# DB15.net
KiCad netlist of a schematic drawn in EAGLE
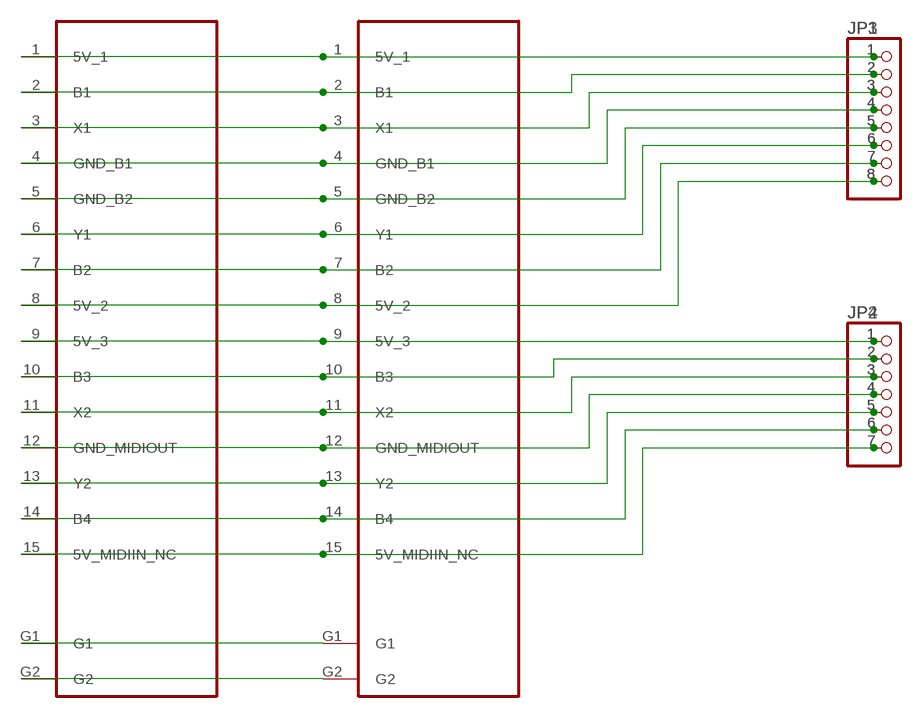
[diagram p0: schematic, sheet 1]

(export (version "E")
  (design (tool "Eeschema 10.0.6"))
  (components
    (comp (ref "JP1")
      (value "PINHD-1X8")
      (footprint "eagle-import:1X08")
      (libsource (lib "eagle-import") (part "PINHD-1X8"))
    )
    (comp (ref "JP2")
      (value "PINHD-1X7")
      (footprint "eagle-import:1X07")
      (libsource (lib "eagle-import") (part "PINHD-1X7"))
    )
    (comp (ref "JP3")
      (value "PINHD-1X8")
      (footprint "eagle-import:1X08")
      (libsource (lib "eagle-import") (part "PINHD-1X8"))
    )
    (comp (ref "JP4")
      (value "PINHD-1X7")
      (footprint "eagle-import:1X07")
      (libsource (lib "eagle-import") (part "PINHD-1X7"))
    )
    (comp (ref "U$1")
      (value "GAMEPORT_15P")
      (footprint "eagle-import:DA15")
      (libsource (lib "eagle-import") (part "GAMEPORT_15P"))
    )
    (comp (ref "U$2")
      (value "GAMEPORT_15P")
      (footprint "eagle-import:DA15")
      (libsource (lib "eagle-import") (part "GAMEPORT_15P"))
    )
  )
  (nets
    (net (code "1") (name "Net-(U$1-5V_1)") (class "Default")
      (node (ref "JP1") (pin "1") (pinfunction "1_1") (pintype "passive"))
      (node (ref "JP3") (pin "1") (pinfunction "1_1") (pintype "passive"))
      (node (ref "U$1") (pin "1") (pinfunction "5V_1_1") (pintype "bidirectional"))
      (node (ref "U$2") (pin "1") (pinfunction "5V_1_1") (pintype "bidirectional"))
    )
    (net (code "2") (name "Net-(U$1-5V_2)") (class "Default")
      (node (ref "JP1") (pin "8") (pinfunction "8_8") (pintype "passive"))
      (node (ref "JP3") (pin "8") (pinfunction "8_8") (pintype "passive"))
      (node (ref "U$1") (pin "8") (pinfunction "5V_2_8") (pintype "bidirectional"))
      (node (ref "U$2") (pin "8") (pinfunction "5V_2_8") (pintype "bidirectional"))
    )
    (net (code "3") (name "Net-(U$1-5V_3)") (class "Default")
      (node (ref "JP2") (pin "1") (pinfunction "1_1") (pintype "passive"))
      (node (ref "JP4") (pin "1") (pinfunction "1_1") (pintype "passive"))
      (node (ref "U$1") (pin "9") (pinfunction "5V_3_9") (pintype "bidirectional"))
      (node (ref "U$2") (pin "9") (pinfunction "5V_3_9") (pintype "bidirectional"))
    )
    (net (code "4") (name "Net-(U$1-5V_MIDIIN_NC)") (class "Default")
      (node (ref "JP2") (pin "7") (pinfunction "7_7") (pintype "passive"))
      (node (ref "JP4") (pin "7") (pinfunction "7_7") (pintype "passive"))
      (node (ref "U$1") (pin "15") (pinfunction "5V_MIDIIN_NC_15") (pintype "bidirectional"))
      (node (ref "U$2") (pin "15") (pinfunction "5V_MIDIIN_NC_15") (pintype "bidirectional"))
    )
    (net (code "5") (name "Net-(U$1-B1)") (class "Default")
      (node (ref "JP1") (pin "2") (pinfunction "2_2") (pintype "passive"))
      (node (ref "JP3") (pin "2") (pinfunction "2_2") (pintype "passive"))
      (node (ref "U$1") (pin "2") (pinfunction "B1_2") (pintype "bidirectional"))
      (node (ref "U$2") (pin "2") (pinfunction "B1_2") (pintype "bidirectional"))
    )
    (net (code "6") (name "Net-(U$1-B2)") (class "Default")
      (node (ref "JP1") (pin "7") (pinfunction "7_7") (pintype "passive"))
      (node (ref "JP3") (pin "7") (pinfunction "7_7") (pintype "passive"))
      (node (ref "U$1") (pin "7") (pinfunction "B2_7") (pintype "bidirectional"))
      (node (ref "U$2") (pin "7") (pinfunction "B2_7") (pintype "bidirectional"))
    )
    (net (code "7") (name "Net-(U$1-B3)") (class "Default")
      (node (ref "JP2") (pin "2") (pinfunction "2_2") (pintype "passive"))
      (node (ref "JP4") (pin "2") (pinfunction "2_2") (pintype "passive"))
      (node (ref "U$1") (pin "10") (pinfunction "B3_10") (pintype "bidirectional"))
      (node (ref "U$2") (pin "10") (pinfunction "B3_10") (pintype "bidirectional"))
    )
    (net (code "8") (name "Net-(U$1-B4)") (class "Default")
      (node (ref "JP2") (pin "6") (pinfunction "6_6") (pintype "passive"))
      (node (ref "JP4") (pin "6") (pinfunction "6_6") (pintype "passive"))
      (node (ref "U$1") (pin "14") (pinfunction "B4_14") (pintype "bidirectional"))
      (node (ref "U$2") (pin "14") (pinfunction "B4_14") (pintype "bidirectional"))
    )
    (net (code "9") (name "Net-(U$1-GND_B1)") (class "Default")
      (node (ref "JP1") (pin "4") (pinfunction "4_4") (pintype "passive"))
      (node (ref "JP3") (pin "4") (pinfunction "4_4") (pintype "passive"))
      (node (ref "U$1") (pin "4") (pinfunction "GND_B1_4") (pintype "bidirectional"))
      (node (ref "U$2") (pin "4") (pinfunction "GND_B1_4") (pintype "bidirectional"))
    )
    (net (code "10") (name "Net-(U$1-GND_B2)") (class "Default")
      (node (ref "JP1") (pin "5") (pinfunction "5_5") (pintype "passive"))
      (node (ref "JP3") (pin "5") (pinfunction "5_5") (pintype "passive"))
      (node (ref "U$1") (pin "5") (pinfunction "GND_B2_5") (pintype "bidirectional"))
      (node (ref "U$2") (pin "5") (pinfunction "GND_B2_5") (pintype "bidirectional"))
    )
    (net (code "11") (name "Net-(U$1-GND_MIDIOUT)") (class "Default")
      (node (ref "JP2") (pin "4") (pinfunction "4_4") (pintype "passive"))
      (node (ref "JP4") (pin "4") (pinfunction "4_4") (pintype "passive"))
      (node (ref "U$1") (pin "12") (pinfunction "GND_MIDIOUT_12") (pintype "bidirectional"))
      (node (ref "U$2") (pin "12") (pinfunction "GND_MIDIOUT_12") (pintype "bidirectional"))
    )
    (net (code "12") (name "Net-(U$1-PadG1)") (class "Default")
      (node (ref "U$1") (pin "G1") (pinfunction "G1_G1") (pintype "bidirectional"))
      (node (ref "U$2") (pin "G1") (pinfunction "G1_G1") (pintype "bidirectional"))
    )
    (net (code "13") (name "Net-(U$1-PadG2)") (class "Default")
      (node (ref "U$1") (pin "G2") (pinfunction "G2_G2") (pintype "bidirectional"))
      (node (ref "U$2") (pin "G2") (pinfunction "G2_G2") (pintype "bidirectional"))
    )
    (net (code "14") (name "Net-(U$1-X1)") (class "Default")
      (node (ref "JP1") (pin "3") (pinfunction "3_3") (pintype "passive"))
      (node (ref "JP3") (pin "3") (pinfunction "3_3") (pintype "passive"))
      (node (ref "U$1") (pin "3") (pinfunction "X1_3") (pintype "bidirectional"))
      (node (ref "U$2") (pin "3") (pinfunction "X1_3") (pintype "bidirectional"))
    )
    (net (code "15") (name "Net-(U$1-X2)") (class "Default")
      (node (ref "JP2") (pin "3") (pinfunction "3_3") (pintype "passive"))
      (node (ref "JP4") (pin "3") (pinfunction "3_3") (pintype "passive"))
      (node (ref "U$1") (pin "11") (pinfunction "X2_11") (pintype "bidirectional"))
      (node (ref "U$2") (pin "11") (pinfunction "X2_11") (pintype "bidirectional"))
    )
    (net (code "16") (name "Net-(U$1-Y1)") (class "Default")
      (node (ref "JP1") (pin "6") (pinfunction "6_6") (pintype "passive"))
      (node (ref "JP3") (pin "6") (pinfunction "6_6") (pintype "passive"))
      (node (ref "U$1") (pin "6") (pinfunction "Y1_6") (pintype "bidirectional"))
      (node (ref "U$2") (pin "6") (pinfunction "Y1_6") (pintype "bidirectional"))
    )
    (net (code "17") (name "Net-(U$1-Y2)") (class "Default")
      (node (ref "JP2") (pin "5") (pinfunction "5_5") (pintype "passive"))
      (node (ref "JP4") (pin "5") (pinfunction "5_5") (pintype "passive"))
      (node (ref "U$1") (pin "13") (pinfunction "Y2_13") (pintype "bidirectional"))
      (node (ref "U$2") (pin "13") (pinfunction "Y2_13") (pintype "bidirectional"))
    )
  )
)
